# meteo_schematic.net
KiCad netlist of a schematic drawn in Altium Designer
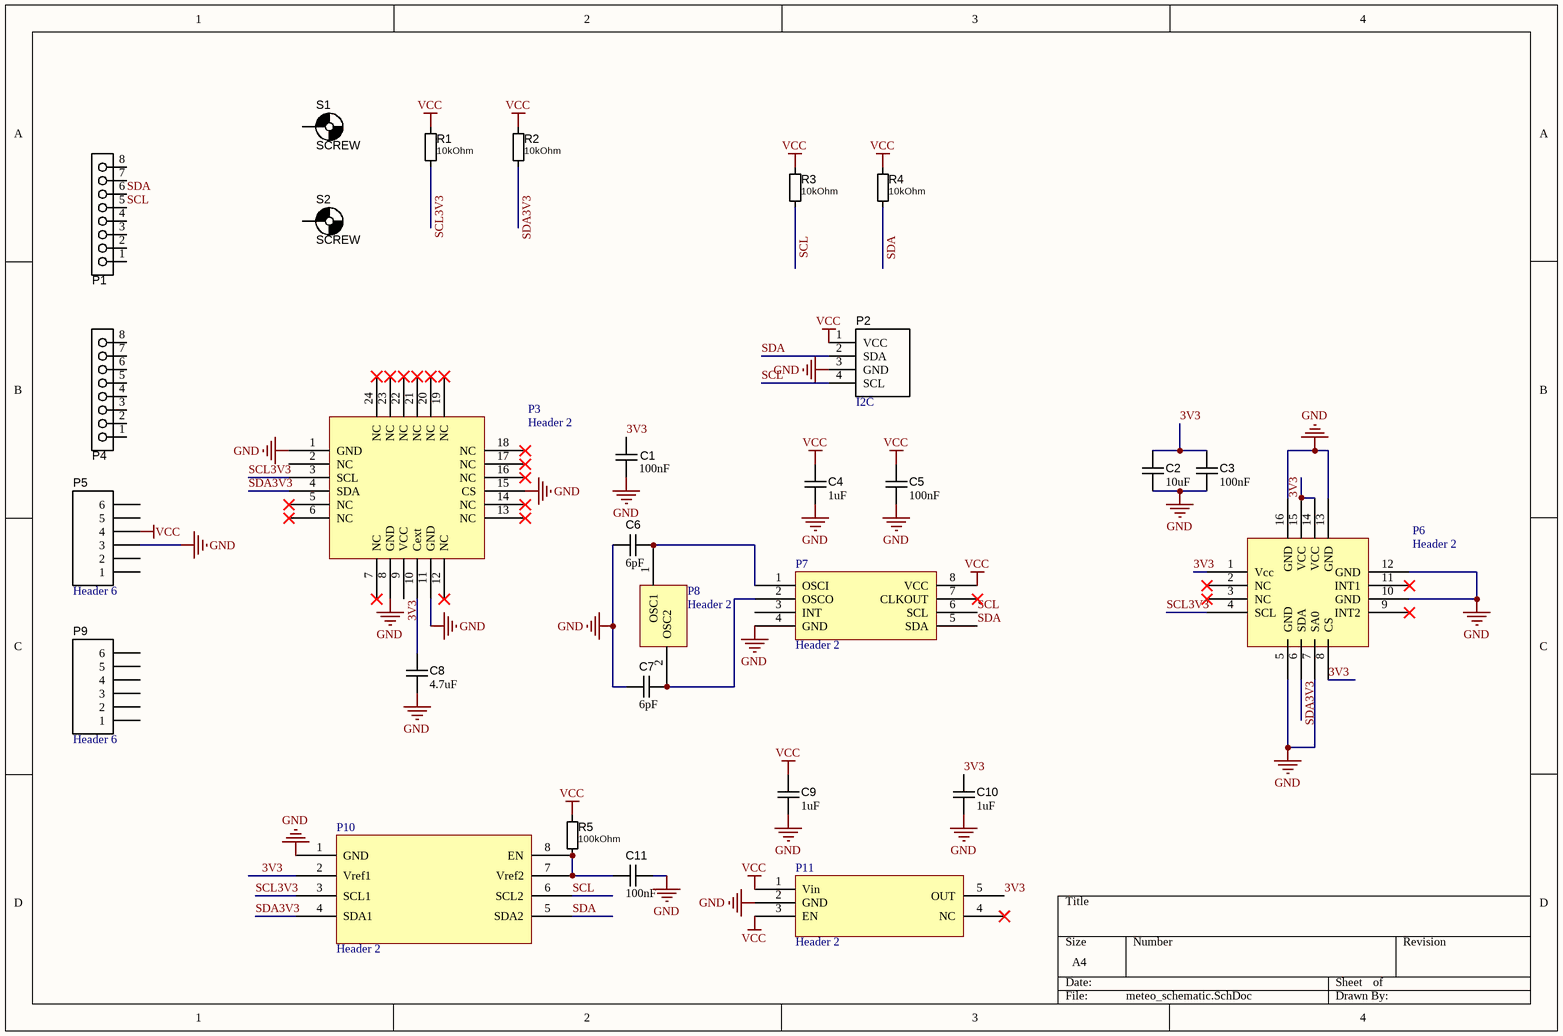
[diagram p0: meteo_schematic.SchDoc]

(export (version "E")
  (design (tool "Eeschema 10.0.6"))
  (components
    (comp (ref "C1")
      (value "100nF")
      (footprint "C/0805")
      (description "Capacitor")
      (fields (field (name "Comment") "C/0805/100nF") (field (name "PUBLISHER") "Altium Limited"))
      (libsource (lib "andylib") (part "C/0805/100nF"))
    )
    (comp (ref "C2")
      (value "10uF")
      (footprint "C/0805")
      (description "Capacitor")
      (fields (field (name "Comment") "C") (field (name "PUBLISHER") "Altium Limited"))
      (libsource (lib "andylib") (part "C"))
    )
    (comp (ref "C3")
      (value "100nF")
      (footprint "C/0805")
      (description "Capacitor")
      (fields (field (name "Comment") "C") (field (name "PUBLISHER") "Altium Limited"))
      (libsource (lib "andylib") (part "C"))
    )
    (comp (ref "C4")
      (value "1uF")
      (footprint "C/0805")
      (description "Capacitor")
      (fields (field (name "Comment") "C/0805/100nF") (field (name "PUBLISHER") "Altium Limited"))
      (libsource (lib "andylib") (part "C/0805/100nF"))
    )
    (comp (ref "C5")
      (value "100nF")
      (footprint "C/0805")
      (description "Capacitor")
      (fields (field (name "Comment") "C/0805/100nF") (field (name "PUBLISHER") "Altium Limited"))
      (libsource (lib "andylib") (part "C/0805/100nF"))
    )
    (comp (ref "C6")
      (value "6pF")
      (footprint "C/0805")
      (description "Capacitor")
      (fields (field (name "Comment") "C") (field (name "PUBLISHER") "Altium Limited"))
      (libsource (lib "andylib") (part "C"))
    )
    (comp (ref "C7")
      (value "6pF")
      (footprint "C/0805")
      (description "Capacitor")
      (fields (field (name "Comment") "C") (field (name "PUBLISHER") "Altium Limited"))
      (libsource (lib "andylib") (part "C"))
    )
    (comp (ref "C8")
      (value "4.7uF")
      (footprint "C/0805")
      (description "Capacitor")
      (fields (field (name "Comment") "C/0805/100nF") (field (name "PUBLISHER") "Altium Limited"))
      (libsource (lib "andylib") (part "C/0805/100nF"))
    )
    (comp (ref "C9")
      (value "1uF")
      (footprint "C/0805")
      (description "Capacitor")
      (fields (field (name "Comment") "C/0805/100nF") (field (name "PUBLISHER") "Altium Limited"))
      (libsource (lib "andylib") (part "C/0805/100nF"))
    )
    (comp (ref "C10")
      (value "1uF")
      (footprint "C/0805")
      (description "Capacitor")
      (fields (field (name "Comment") "C/0805/100nF") (field (name "PUBLISHER") "Altium Limited"))
      (libsource (lib "andylib") (part "C/0805/100nF"))
    )
    (comp (ref "C11")
      (value "100nF")
      (footprint "C/0805")
      (description "Capacitor")
      (fields (field (name "Comment") "C/0805/100nF") (field (name "PUBLISHER") "Altium Limited"))
      (libsource (lib "andylib") (part "C/0805/100nF"))
    )
    (comp (ref "P1")
      (value "Header 8")
      (footprint "Arduino Pad 8")
      (description "Header, 8-Pin")
      (fields (field (name "PUBLISHER") "Altium Limited"))
      (libsource (lib "andylib") (part "Header 8"))
    )
    (comp (ref "P2")
      (value "I2C")
      (footprint "TYCO/215079-4")
      (description "Micromatch I2C Connector")
      (libsource (lib "andylib") (part "Micromatch-I2C"))
    )
    (comp (ref "P3")
      (value "Header 2")
      (footprint "Si7005")
      (description "Header, 2-Pin")
      (fields (field (name "PUBLISHER") "Altium Limited"))
      (libsource (lib "marcolib") (part "Si7005"))
    )
    (comp (ref "P4")
      (value "Header 8")
      (footprint "Arduino Pad 8")
      (description "Header, 8-Pin")
      (fields (field (name "PUBLISHER") "Altium Limited"))
      (libsource (lib "andylib") (part "Header 8"))
    )
    (comp (ref "P5")
      (value "Header 6")
      (footprint "Arduino Pad 6")
      (description "Header, 6-Pin")
      (fields (field (name "PUBLISHER") "Altium Limited"))
      (libsource (lib "andylib") (part "Header 6"))
    )
    (comp (ref "P6")
      (value "Header 2")
      (footprint "HCLGA-16L")
      (description "Header, 2-Pin")
      (fields (field (name "PUBLISHER") "Altium Limited"))
      (libsource (lib "marcolib") (part "Barometer LPS331AP"))
    )
    (comp (ref "P7")
      (value "Header 2")
      (footprint "PCA8565TS")
      (description "Header, 2-Pin")
      (fields (field (name "PUBLISHER") "Altium Limited"))
      (libsource (lib "marcolib") (part "PCA8565"))
    )
    (comp (ref "P8")
      (value "Header 2")
      (footprint "Quartz")
      (description "Header, 2-Pin")
      (fields (field (name "PUBLISHER") "Altium Limited"))
      (libsource (lib "marcolib") (part "Xtal32768khz"))
    )
    (comp (ref "P9")
      (value "Header 6")
      (footprint "Arduino Pad 6")
      (description "Header, 6-Pin")
      (fields (field (name "PUBLISHER") "Altium Limited"))
      (libsource (lib "andylib") (part "Header 6"))
    )
    (comp (ref "P10")
      (value "Header 2")
      (footprint "PCA9306DP1")
      (description "Header, 2-Pin")
      (fields (field (name "PUBLISHER") "Altium Limited"))
      (libsource (lib "marcolib") (part "PCA9306DP1"))
    )
    (comp (ref "P11")
      (value "Header 2")
      (footprint "TLV70033DDCR")
      (description "Header, 2-Pin")
      (fields (field (name "PUBLISHER") "Altium Limited"))
      (libsource (lib "marcolib") (part "TLV700xx"))
    )
    (comp (ref "R1")
      (value "10kOhm")
      (footprint "R/0805")
      (description "Resistor")
      (fields (field (name "PUBLISHER") "Altium Limited"))
      (libsource (lib "andylib") (part "R"))
    )
    (comp (ref "R2")
      (value "10kOhm")
      (footprint "R/0805")
      (description "Resistor")
      (fields (field (name "PUBLISHER") "Altium Limited"))
      (libsource (lib "andylib") (part "R"))
    )
    (comp (ref "R3")
      (value "10kOhm")
      (footprint "R/0805")
      (description "Resistor")
      (fields (field (name "PUBLISHER") "Altium Limited"))
      (libsource (lib "andylib") (part "R"))
    )
    (comp (ref "R4")
      (value "10kOhm")
      (footprint "R/0805")
      (description "Resistor")
      (fields (field (name "PUBLISHER") "Altium Limited"))
      (libsource (lib "andylib") (part "R"))
    )
    (comp (ref "R5")
      (value "100kOhm")
      (footprint "R/0805")
      (description "Resistor")
      (fields (field (name "PUBLISHER") "Altium Limited"))
      (libsource (lib "andylib") (part "R"))
    )
    (comp (ref "S1") (value "SCREW") (footprint "HW/SCREW/M2_5") (libsource (lib "andylib") (part "SCREW")))
    (comp (ref "S2") (value "SCREW") (footprint "HW/SCREW/M2_5") (libsource (lib "andylib") (part "SCREW")))
  )
  (nets
    (net (code "1") (name "/3V3") (class "Default")
      (node (ref "C1") (pin "2") (pinfunction "2_2") (pintype "passive"))
      (node (ref "C10") (pin "2") (pinfunction "2_2") (pintype "passive"))
      (node (ref "C2") (pin "2") (pinfunction "2_2") (pintype "passive"))
      (node (ref "C3") (pin "2") (pinfunction "2_2") (pintype "passive"))
      (node (ref "P10") (pin "2") (pinfunction "Vref1_2") (pintype "passive"))
      (node (ref "P11") (pin "5") (pinfunction "OUT_5") (pintype "passive"))
      (node (ref "P3") (pin "9") (pinfunction "VCC_9") (pintype "passive"))
      (node (ref "P6") (pin "1") (pinfunction "Vcc_1") (pintype "passive"))
      (node (ref "P6") (pin "14") (pinfunction "VCC_14") (pintype "passive"))
      (node (ref "P6") (pin "15") (pinfunction "VCC_15") (pintype "passive"))
      (node (ref "P6") (pin "8") (pinfunction "CS_8") (pintype "passive"))
    )
    (net (code "2") (name "/SCL") (class "Default")
      (node (ref "P1") (pin "5") (pinfunction "5_5") (pintype "passive"))
      (node (ref "P10") (pin "6") (pinfunction "SCL2_6") (pintype "passive"))
      (node (ref "P2") (pin "4") (pinfunction "SCL_4") (pintype "passive"))
      (node (ref "P7") (pin "6") (pinfunction "SCL_6") (pintype "passive"))
      (node (ref "R3") (pin "1") (pinfunction "1_1") (pintype "passive"))
    )
    (net (code "3") (name "/SCL3V3") (class "Default")
      (node (ref "P10") (pin "3") (pinfunction "SCL1_3") (pintype "passive"))
      (node (ref "P3") (pin "3") (pinfunction "SCL_3") (pintype "passive"))
      (node (ref "P6") (pin "4") (pinfunction "SCL_4") (pintype "passive"))
      (node (ref "R1") (pin "1") (pinfunction "1_1") (pintype "passive"))
    )
    (net (code "4") (name "/SDA") (class "Default")
      (node (ref "P1") (pin "6") (pinfunction "6_6") (pintype "passive"))
      (node (ref "P10") (pin "5") (pinfunction "SDA2_5") (pintype "passive"))
      (node (ref "P2") (pin "2") (pinfunction "SDA_2") (pintype "passive"))
      (node (ref "P7") (pin "5") (pinfunction "SDA_5") (pintype "passive"))
      (node (ref "R4") (pin "1") (pinfunction "1_1") (pintype "passive"))
    )
    (net (code "5") (name "/SDA3V3") (class "Default")
      (node (ref "P10") (pin "4") (pinfunction "SDA1_4") (pintype "passive"))
      (node (ref "P3") (pin "4") (pinfunction "SDA_4") (pintype "passive"))
      (node (ref "P6") (pin "6") (pinfunction "SDA_6") (pintype "passive"))
      (node (ref "R2") (pin "1") (pinfunction "1_1") (pintype "passive"))
    )
    (net (code "6") (name "GND") (class "Default")
      (node (ref "C1") (pin "1") (pinfunction "1_1") (pintype "passive"))
      (node (ref "C10") (pin "1") (pinfunction "1_1") (pintype "passive"))
      (node (ref "C11") (pin "1") (pinfunction "1_1") (pintype "passive"))
      (node (ref "C2") (pin "1") (pinfunction "1_1") (pintype "passive"))
      (node (ref "C3") (pin "1") (pinfunction "1_1") (pintype "passive"))
      (node (ref "C4") (pin "1") (pinfunction "1_1") (pintype "passive"))
      (node (ref "C5") (pin "1") (pinfunction "1_1") (pintype "passive"))
      (node (ref "C6") (pin "2") (pinfunction "2_2") (pintype "passive"))
      (node (ref "C7") (pin "2") (pinfunction "2_2") (pintype "passive"))
      (node (ref "C8") (pin "1") (pinfunction "1_1") (pintype "passive"))
      (node (ref "C9") (pin "1") (pinfunction "1_1") (pintype "passive"))
      (node (ref "P10") (pin "1") (pinfunction "GND_1") (pintype "passive"))
      (node (ref "P11") (pin "2") (pinfunction "GND_2") (pintype "passive"))
      (node (ref "P2") (pin "3") (pinfunction "GND_3") (pintype "passive"))
      (node (ref "P3") (pin "1") (pinfunction "GND_1") (pintype "passive"))
      (node (ref "P3") (pin "11") (pinfunction "GND_11") (pintype "passive"))
      (node (ref "P3") (pin "15") (pinfunction "CS_15") (pintype "passive"))
      (node (ref "P3") (pin "8") (pinfunction "GND_8") (pintype "passive"))
      (node (ref "P5") (pin "3") (pinfunction "3_3") (pintype "passive"))
      (node (ref "P6") (pin "10") (pinfunction "GND_10") (pintype "passive"))
      (node (ref "P6") (pin "12") (pinfunction "GND_12") (pintype "passive"))
      (node (ref "P6") (pin "13") (pinfunction "GND_13") (pintype "passive"))
      (node (ref "P6") (pin "16") (pinfunction "GND_16") (pintype "passive"))
      (node (ref "P6") (pin "5") (pinfunction "GND_5") (pintype "passive"))
      (node (ref "P6") (pin "7") (pinfunction "SA0_7") (pintype "passive"))
      (node (ref "P7") (pin "4") (pinfunction "GND_4") (pintype "passive"))
    )
    (net (code "7") (name "Net-(P3-Cext)") (class "Default")
      (node (ref "C8") (pin "2") (pinfunction "2_2") (pintype "passive"))
      (node (ref "P3") (pin "10") (pinfunction "Cext_10") (pintype "passive"))
    )
    (net (code "8") (name "Net-(P7-OSCI)") (class "Default")
      (node (ref "C6") (pin "1") (pinfunction "1_1") (pintype "passive"))
      (node (ref "P7") (pin "1") (pinfunction "OSCI_1") (pintype "passive"))
      (node (ref "P8") (pin "1") (pinfunction "OSC1_1") (pintype "passive"))
    )
    (net (code "9") (name "Net-(P7-OSCO)") (class "Default")
      (node (ref "C7") (pin "1") (pinfunction "1_1") (pintype "passive"))
      (node (ref "P7") (pin "2") (pinfunction "OSCO_2") (pintype "passive"))
      (node (ref "P8") (pin "2") (pinfunction "OSC2_2") (pintype "passive"))
    )
    (net (code "10") (name "Net-(P10-EN)") (class "Default")
      (node (ref "C11") (pin "2") (pinfunction "2_2") (pintype "passive"))
      (node (ref "P10") (pin "7") (pinfunction "Vref2_7") (pintype "passive"))
      (node (ref "P10") (pin "8") (pinfunction "EN_8") (pintype "passive"))
      (node (ref "R5") (pin "1") (pinfunction "1_1") (pintype "passive"))
    )
    (net (code "11") (name "VCC") (class "Default")
      (node (ref "C4") (pin "2") (pinfunction "2_2") (pintype "passive"))
      (node (ref "C5") (pin "2") (pinfunction "2_2") (pintype "passive"))
      (node (ref "C9") (pin "2") (pinfunction "2_2") (pintype "passive"))
      (node (ref "P11") (pin "1") (pinfunction "Vin_1") (pintype "passive"))
      (node (ref "P11") (pin "3") (pinfunction "EN_3") (pintype "passive"))
      (node (ref "P2") (pin "1") (pinfunction "VCC_1") (pintype "passive"))
      (node (ref "P5") (pin "4") (pinfunction "4_4") (pintype "passive"))
      (node (ref "P7") (pin "8") (pinfunction "VCC_8") (pintype "passive"))
      (node (ref "R1") (pin "2") (pinfunction "2_2") (pintype "passive"))
      (node (ref "R2") (pin "2") (pinfunction "2_2") (pintype "passive"))
      (node (ref "R3") (pin "2") (pinfunction "2_2") (pintype "passive"))
      (node (ref "R4") (pin "2") (pinfunction "2_2") (pintype "passive"))
      (node (ref "R5") (pin "2") (pinfunction "2_2") (pintype "passive"))
    )
    (net (code "12") (name "unconnected-(P1-Pad1)") (class "Default")
      (node (ref "P1") (pin "1") (pinfunction "1_1") (pintype "passive"))
    )
    (net (code "13") (name "unconnected-(P1-Pad2)") (class "Default")
      (node (ref "P1") (pin "2") (pinfunction "2_2") (pintype "passive"))
    )
    (net (code "14") (name "unconnected-(P1-Pad3)") (class "Default")
      (node (ref "P1") (pin "3") (pinfunction "3_3") (pintype "passive"))
    )
    (net (code "15") (name "unconnected-(P1-Pad4)") (class "Default")
      (node (ref "P1") (pin "4") (pinfunction "4_4") (pintype "passive"))
    )
    (net (code "16") (name "unconnected-(P1-Pad7)") (class "Default")
      (node (ref "P1") (pin "7") (pinfunction "7_7") (pintype "passive"))
    )
    (net (code "17") (name "unconnected-(P1-Pad8)") (class "Default")
      (node (ref "P1") (pin "8") (pinfunction "8_8") (pintype "passive"))
    )
    (net (code "18") (name "unconnected-(P3-NC-Pad2)") (class "Default")
      (node (ref "P3") (pin "2") (pinfunction "NC_2") (pintype "passive"))
    )
    (net (code "19") (name "unconnected-(P3-NC-Pad5)") (class "Default")
      (node (ref "P3") (pin "5") (pinfunction "NC_5") (pintype "passive+no_connect"))
    )
    (net (code "20") (name "unconnected-(P3-NC-Pad6)") (class "Default")
      (node (ref "P3") (pin "6") (pinfunction "NC_6") (pintype "passive+no_connect"))
    )
    (net (code "21") (name "unconnected-(P3-NC-Pad7)") (class "Default")
      (node (ref "P3") (pin "7") (pinfunction "NC_7") (pintype "passive+no_connect"))
    )
    (net (code "22") (name "unconnected-(P3-NC-Pad12)") (class "Default")
      (node (ref "P3") (pin "12") (pinfunction "NC_12") (pintype "passive+no_connect"))
    )
    (net (code "23") (name "unconnected-(P3-NC-Pad13)") (class "Default")
      (node (ref "P3") (pin "13") (pinfunction "NC_13") (pintype "passive+no_connect"))
    )
    (net (code "24") (name "unconnected-(P3-NC-Pad14)") (class "Default")
      (node (ref "P3") (pin "14") (pinfunction "NC_14") (pintype "passive+no_connect"))
    )
    (net (code "25") (name "unconnected-(P3-NC-Pad16)") (class "Default")
      (node (ref "P3") (pin "16") (pinfunction "NC_16") (pintype "passive+no_connect"))
    )
    (net (code "26") (name "unconnected-(P3-NC-Pad17)") (class "Default")
      (node (ref "P3") (pin "17") (pinfunction "NC_17") (pintype "passive+no_connect"))
    )
    (net (code "27") (name "unconnected-(P3-NC-Pad18)") (class "Default")
      (node (ref "P3") (pin "18") (pinfunction "NC_18") (pintype "passive+no_connect"))
    )
    (net (code "28") (name "unconnected-(P3-NC-Pad19)") (class "Default")
      (node (ref "P3") (pin "19") (pinfunction "NC_19") (pintype "passive+no_connect"))
    )
    (net (code "29") (name "unconnected-(P3-NC-Pad20)") (class "Default")
      (node (ref "P3") (pin "20") (pinfunction "NC_20") (pintype "passive+no_connect"))
    )
    (net (code "30") (name "unconnected-(P3-NC-Pad21)") (class "Default")
      (node (ref "P3") (pin "21") (pinfunction "NC_21") (pintype "passive+no_connect"))
    )
    (net (code "31") (name "unconnected-(P3-NC-Pad22)") (class "Default")
      (node (ref "P3") (pin "22") (pinfunction "NC_22") (pintype "passive+no_connect"))
    )
    (net (code "32") (name "unconnected-(P3-NC-Pad23)") (class "Default")
      (node (ref "P3") (pin "23") (pinfunction "NC_23") (pintype "passive+no_connect"))
    )
    (net (code "33") (name "unconnected-(P3-NC-Pad24)") (class "Default")
      (node (ref "P3") (pin "24") (pinfunction "NC_24") (pintype "passive+no_connect"))
    )
    (net (code "34") (name "unconnected-(P4-Pad1)") (class "Default")
      (node (ref "P4") (pin "1") (pinfunction "1_1") (pintype "passive"))
    )
    (net (code "35") (name "unconnected-(P4-Pad2)") (class "Default")
      (node (ref "P4") (pin "2") (pinfunction "2_2") (pintype "passive"))
    )
    (net (code "36") (name "unconnected-(P4-Pad3)") (class "Default")
      (node (ref "P4") (pin "3") (pinfunction "3_3") (pintype "passive"))
    )
    (net (code "37") (name "unconnected-(P4-Pad4)") (class "Default")
      (node (ref "P4") (pin "4") (pinfunction "4_4") (pintype "passive"))
    )
    (net (code "38") (name "unconnected-(P4-Pad5)") (class "Default")
      (node (ref "P4") (pin "5") (pinfunction "5_5") (pintype "passive"))
    )
    (net (code "39") (name "unconnected-(P4-Pad6)") (class "Default")
      (node (ref "P4") (pin "6") (pinfunction "6_6") (pintype "passive"))
    )
    (net (code "40") (name "unconnected-(P4-Pad7)") (class "Default")
      (node (ref "P4") (pin "7") (pinfunction "7_7") (pintype "passive"))
    )
    (net (code "41") (name "unconnected-(P4-Pad8)") (class "Default")
      (node (ref "P4") (pin "8") (pinfunction "8_8") (pintype "passive"))
    )
    (net (code "42") (name "unconnected-(P5-Pad1)") (class "Default")
      (node (ref "P5") (pin "1") (pinfunction "1_1") (pintype "passive"))
    )
    (net (code "43") (name "unconnected-(P5-Pad2)") (class "Default")
      (node (ref "P5") (pin "2") (pinfunction "2_2") (pintype "passive"))
    )
    (net (code "44") (name "unconnected-(P5-Pad5)") (class "Default")
      (node (ref "P5") (pin "5") (pinfunction "5_5") (pintype "passive"))
    )
    (net (code "45") (name "unconnected-(P5-Pad6)") (class "Default")
      (node (ref "P5") (pin "6") (pinfunction "6_6") (pintype "passive"))
    )
    (net (code "46") (name "unconnected-(P6-INT1-Pad11)") (class "Default")
      (node (ref "P6") (pin "11") (pinfunction "INT1_11") (pintype "passive+no_connect"))
    )
    (net (code "47") (name "unconnected-(P6-INT2-Pad9)") (class "Default")
      (node (ref "P6") (pin "9") (pinfunction "INT2_9") (pintype "passive+no_connect"))
    )
    (net (code "48") (name "unconnected-(P6-NC-Pad2)") (class "Default")
      (node (ref "P6") (pin "2") (pinfunction "NC_2") (pintype "passive+no_connect"))
    )
    (net (code "49") (name "unconnected-(P6-NC-Pad3)") (class "Default")
      (node (ref "P6") (pin "3") (pinfunction "NC_3") (pintype "passive+no_connect"))
    )
    (net (code "50") (name "unconnected-(P7-CLKOUT-Pad7)") (class "Default")
      (node (ref "P7") (pin "7") (pinfunction "CLKOUT_7") (pintype "passive+no_connect"))
    )
    (net (code "51") (name "unconnected-(P7-INT-Pad3)") (class "Default")
      (node (ref "P7") (pin "3") (pinfunction "INT_3") (pintype "passive"))
    )
    (net (code "52") (name "unconnected-(P9-Pad1)") (class "Default")
      (node (ref "P9") (pin "1") (pinfunction "1_1") (pintype "passive"))
    )
    (net (code "53") (name "unconnected-(P9-Pad2)") (class "Default")
      (node (ref "P9") (pin "2") (pinfunction "2_2") (pintype "passive"))
    )
    (net (code "54") (name "unconnected-(P9-Pad3)") (class "Default")
      (node (ref "P9") (pin "3") (pinfunction "3_3") (pintype "passive"))
    )
    (net (code "55") (name "unconnected-(P9-Pad4)") (class "Default")
      (node (ref "P9") (pin "4") (pinfunction "4_4") (pintype "passive"))
    )
    (net (code "56") (name "unconnected-(P9-Pad5)") (class "Default")
      (node (ref "P9") (pin "5") (pinfunction "5_5") (pintype "passive"))
    )
    (net (code "57") (name "unconnected-(P9-Pad6)") (class "Default")
      (node (ref "P9") (pin "6") (pinfunction "6_6") (pintype "passive"))
    )
    (net (code "58") (name "unconnected-(P11-NC-Pad4)") (class "Default")
      (node (ref "P11") (pin "4") (pinfunction "NC_4") (pintype "passive+no_connect"))
    )
    (net (code "59") (name "unconnected-(S1-Pad1)") (class "Default")
      (node (ref "S1") (pin "1") (pinfunction "1_1") (pintype "passive"))
    )
    (net (code "60") (name "unconnected-(S2-Pad1)") (class "Default")
      (node (ref "S2") (pin "1") (pinfunction "1_1") (pintype "passive"))
    )
  )
)
